# Board_V_1C.net
KiCad netlist of a schematic drawn in EAGLE
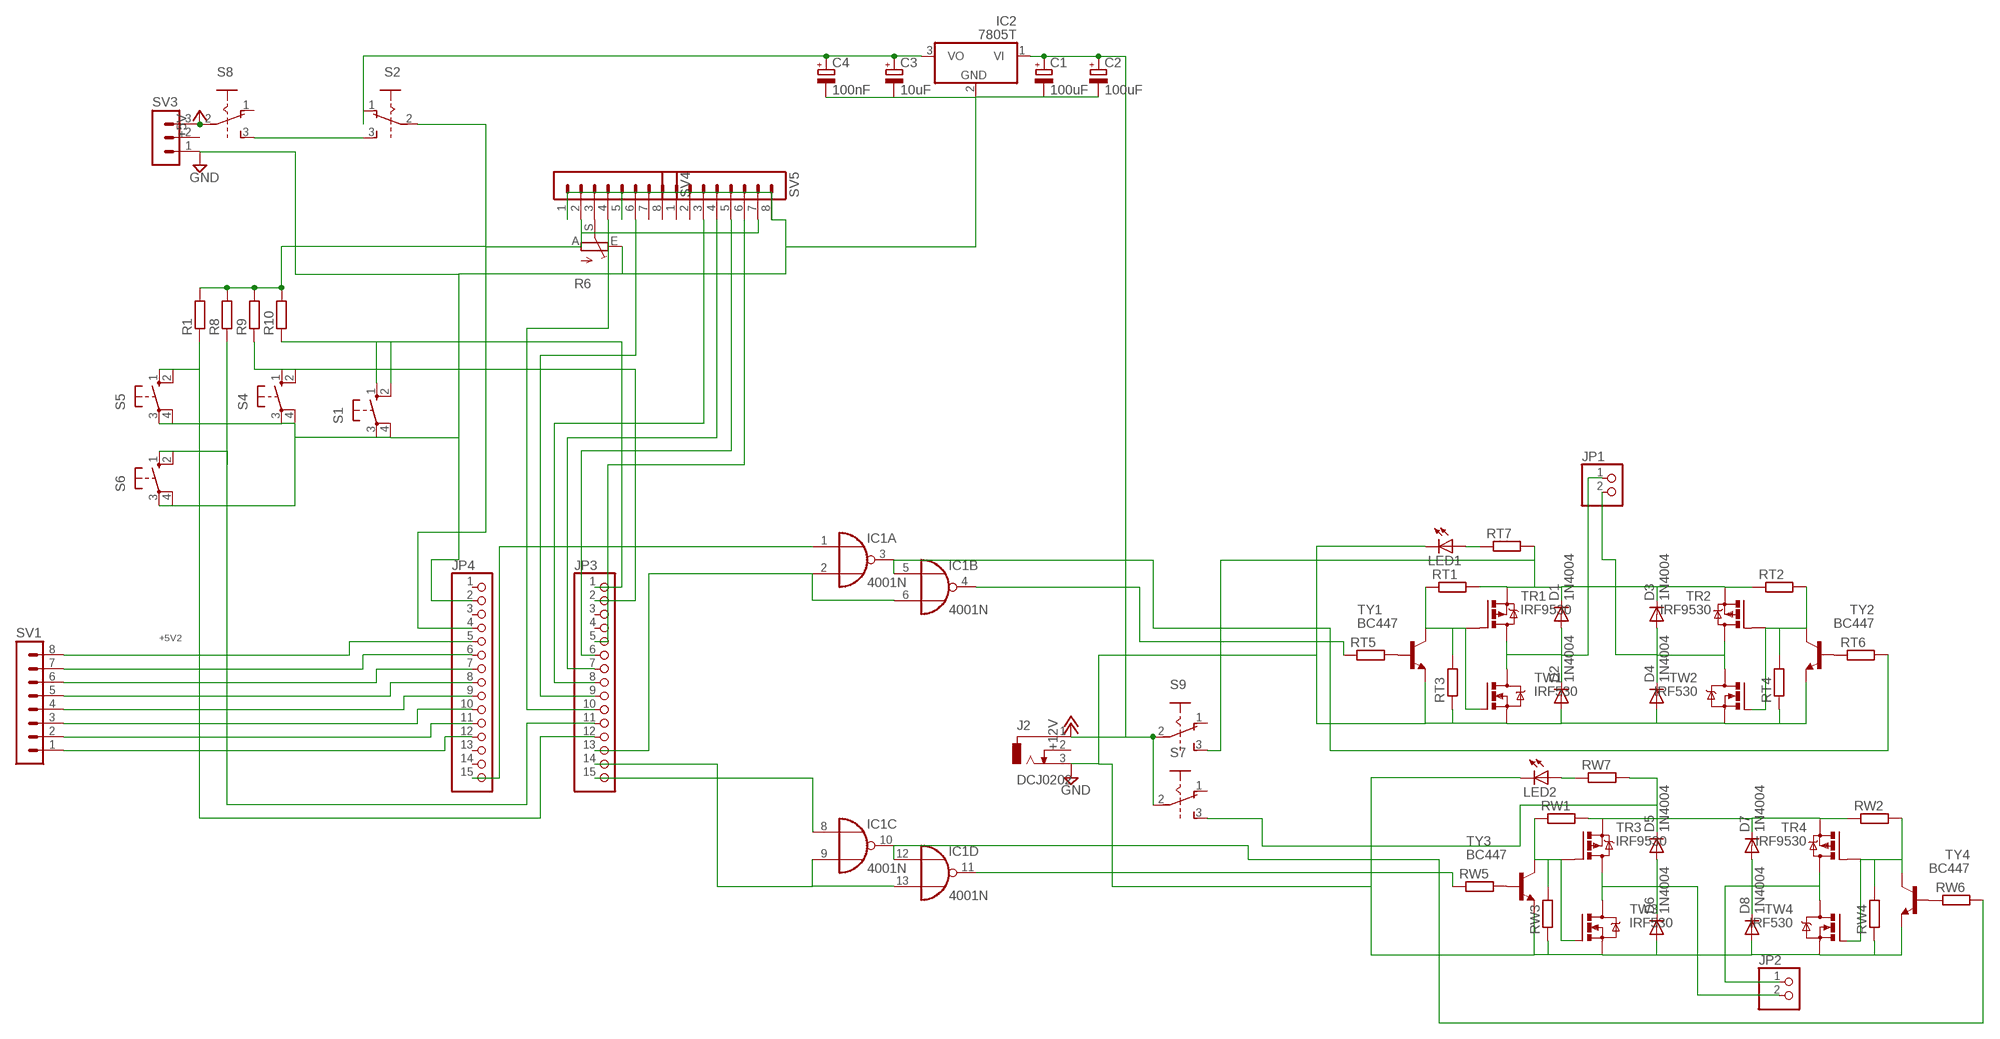
[diagram p0: schematic, sheet 1]

(export (version "E")
  (design (tool "Eeschema 10.0.6"))
  (components
    (comp (ref "C1")
      (value "100uF")
      (footprint "eagle-import:E2,5-6")
      (libsource (lib "eagle-import") (part "CPOL-EUE2.5-6"))
    )
    (comp (ref "C2")
      (value "100uF")
      (footprint "eagle-import:E2,5-6")
      (libsource (lib "eagle-import") (part "CPOL-EUE2.5-6"))
    )
    (comp (ref "C3")
      (value "10uF")
      (footprint "eagle-import:E2,5-6")
      (libsource (lib "eagle-import") (part "CPOL-EUE2.5-6"))
    )
    (comp (ref "C4")
      (value "100nF")
      (footprint "eagle-import:E2,5-6")
      (libsource (lib "eagle-import") (part "CPOL-EUE2.5-6"))
    )
    (comp (ref "D1")
      (value "1N4004")
      (footprint "eagle-import:DO41-10")
      (libsource (lib "eagle-import") (part "1N4004"))
    )
    (comp (ref "D2")
      (value "1N4004")
      (footprint "eagle-import:DO41-10")
      (libsource (lib "eagle-import") (part "1N4004"))
    )
    (comp (ref "D3")
      (value "1N4004")
      (footprint "eagle-import:DO41-10")
      (libsource (lib "eagle-import") (part "1N4004"))
    )
    (comp (ref "D4")
      (value "1N4004")
      (footprint "eagle-import:DO41-10")
      (libsource (lib "eagle-import") (part "1N4004"))
    )
    (comp (ref "D5")
      (value "1N4004")
      (footprint "eagle-import:DO41-10")
      (libsource (lib "eagle-import") (part "1N4004"))
    )
    (comp (ref "D6")
      (value "1N4004")
      (footprint "eagle-import:DO41-10")
      (libsource (lib "eagle-import") (part "1N4004"))
    )
    (comp (ref "D7")
      (value "1N4004")
      (footprint "eagle-import:DO41-10")
      (libsource (lib "eagle-import") (part "1N4004"))
    )
    (comp (ref "D8")
      (value "1N4004")
      (footprint "eagle-import:DO41-10")
      (libsource (lib "eagle-import") (part "1N4004"))
    )
    (comp (ref "IC1")
      (value "4001N")
      (footprint "eagle-import:DIL14")
      (libsource (lib "eagle-import") (part "4001N"))
    )
    (comp (ref "IC2")
      (value "7805T")
      (footprint "eagle-import:TO220H")
      (libsource (lib "eagle-import") (part "78T05"))
    )
    (comp (ref "J2")
      (value "DCJ0202")
      (footprint "eagle-import:DCJ0202")
      (libsource (lib "eagle-import") (part "DCJ0202"))
    )
    (comp (ref "JP1")
      (value "PINHD-1X2")
      (footprint "eagle-import:1X02")
      (libsource (lib "eagle-import") (part "PINHD-1X2"))
    )
    (comp (ref "JP2")
      (value "PINHD-1X2")
      (footprint "eagle-import:1X02")
      (libsource (lib "eagle-import") (part "PINHD-1X2"))
    )
    (comp (ref "JP3")
      (value "PINHD-1X15")
      (footprint "eagle-import:1X15")
      (libsource (lib "eagle-import") (part "PINHD-1X15"))
    )
    (comp (ref "JP4")
      (value "PINHD-1X15")
      (footprint "eagle-import:1X15")
      (libsource (lib "eagle-import") (part "PINHD-1X15"))
    )
    (comp (ref "LED1")
      (value "LED5MM")
      (footprint "eagle-import:LED5MM")
      (libsource (lib "eagle-import") (part "LED5MM"))
    )
    (comp (ref "LED2")
      (value "LED5MM")
      (footprint "eagle-import:LED5MM")
      (libsource (lib "eagle-import") (part "LED5MM"))
    )
    (comp (ref "R1")
      (value "R-EU_0204/7")
      (footprint "eagle-import:0204_7")
      (libsource (lib "eagle-import") (part "R-EU_0204/7"))
    )
    (comp (ref "R6")
      (value "TRIM_EU-B25P")
      (footprint "eagle-import:B25P")
      (libsource (lib "eagle-import") (part "TRIM_EU-B25P"))
    )
    (comp (ref "R8")
      (value "R-EU_0204/7")
      (footprint "eagle-import:0204_7")
      (libsource (lib "eagle-import") (part "R-EU_0204/7"))
    )
    (comp (ref "R9")
      (value "R-EU_0204/7")
      (footprint "eagle-import:0204_7")
      (libsource (lib "eagle-import") (part "R-EU_0204/7"))
    )
    (comp (ref "R10")
      (value "R-EU_0204/7")
      (footprint "eagle-import:0204_7")
      (libsource (lib "eagle-import") (part "R-EU_0204/7"))
    )
    (comp (ref "RT1")
      (value "R-EU_0207/7")
      (footprint "eagle-import:0207_7")
      (libsource (lib "eagle-import") (part "R-EU_0207/7"))
    )
    (comp (ref "RT2")
      (value "R-EU_0207/7")
      (footprint "eagle-import:0207_7")
      (libsource (lib "eagle-import") (part "R-EU_0207/7"))
    )
    (comp (ref "RT3")
      (value "R-EU_0207/7")
      (footprint "eagle-import:0207_7")
      (libsource (lib "eagle-import") (part "R-EU_0207/7"))
    )
    (comp (ref "RT4")
      (value "R-EU_0207/7")
      (footprint "eagle-import:0207_7")
      (libsource (lib "eagle-import") (part "R-EU_0207/7"))
    )
    (comp (ref "RT5")
      (value "R-EU_0207/7")
      (footprint "eagle-import:0207_7")
      (libsource (lib "eagle-import") (part "R-EU_0207/7"))
    )
    (comp (ref "RT6")
      (value "R-EU_0207/7")
      (footprint "eagle-import:0207_7")
      (libsource (lib "eagle-import") (part "R-EU_0207/7"))
    )
    (comp (ref "RT7")
      (value "R-EU_0207/7")
      (footprint "eagle-import:0207_7")
      (libsource (lib "eagle-import") (part "R-EU_0207/7"))
    )
    (comp (ref "RW1")
      (value "R-EU_0207/7")
      (footprint "eagle-import:0207_7")
      (libsource (lib "eagle-import") (part "R-EU_0207/7"))
    )
    (comp (ref "RW2")
      (value "R-EU_0207/7")
      (footprint "eagle-import:0207_7")
      (libsource (lib "eagle-import") (part "R-EU_0207/7"))
    )
    (comp (ref "RW3")
      (value "R-EU_0207/7")
      (footprint "eagle-import:0207_7")
      (libsource (lib "eagle-import") (part "R-EU_0207/7"))
    )
    (comp (ref "RW4")
      (value "R-EU_0207/7")
      (footprint "eagle-import:0207_7")
      (libsource (lib "eagle-import") (part "R-EU_0207/7"))
    )
    (comp (ref "RW5")
      (value "R-EU_0207/7")
      (footprint "eagle-import:0207_7")
      (libsource (lib "eagle-import") (part "R-EU_0207/7"))
    )
    (comp (ref "RW6")
      (value "R-EU_0207/7")
      (footprint "eagle-import:0207_7")
      (libsource (lib "eagle-import") (part "R-EU_0207/7"))
    )
    (comp (ref "RW7")
      (value "R-EU_0207/7")
      (footprint "eagle-import:0207_7")
      (libsource (lib "eagle-import") (part "R-EU_0207/7"))
    )
    (comp (ref "S1")
      (value "10-XX")
      (footprint "eagle-import:B3F-10XX")
      (libsource (lib "eagle-import") (part "10-XX"))
    )
    (comp (ref "S2")
      (value "A68-A31")
      (footprint "eagle-import:A68-A31")
      (libsource (lib "eagle-import") (part "A68-A31"))
    )
    (comp (ref "S4")
      (value "10-XX")
      (footprint "eagle-import:B3F-10XX")
      (libsource (lib "eagle-import") (part "10-XX"))
    )
    (comp (ref "S5")
      (value "10-XX")
      (footprint "eagle-import:B3F-10XX")
      (libsource (lib "eagle-import") (part "10-XX"))
    )
    (comp (ref "S6")
      (value "10-XX")
      (footprint "eagle-import:B3F-10XX")
      (libsource (lib "eagle-import") (part "10-XX"))
    )
    (comp (ref "S7")
      (value "A68-A31")
      (footprint "eagle-import:A68-A31")
      (libsource (lib "eagle-import") (part "A68-A31"))
    )
    (comp (ref "S8")
      (value "A68-A31")
      (footprint "eagle-import:A68-A31")
      (libsource (lib "eagle-import") (part "A68-A31"))
    )
    (comp (ref "S9")
      (value "A68-A31")
      (footprint "eagle-import:A68-A31")
      (libsource (lib "eagle-import") (part "A68-A31"))
    )
    (comp (ref "SV1")
      (value "MA08-1")
      (footprint "eagle-import:MA08-1")
      (libsource (lib "eagle-import") (part "MA08-1"))
    )
    (comp (ref "SV3")
      (value "MA03-1")
      (footprint "eagle-import:MA03-1")
      (libsource (lib "eagle-import") (part "MA03-1"))
    )
    (comp (ref "SV4")
      (value "MA08-1")
      (footprint "eagle-import:MA08-1")
      (libsource (lib "eagle-import") (part "MA08-1"))
    )
    (comp (ref "SV5")
      (value "MA08-1")
      (footprint "eagle-import:MA08-1")
      (libsource (lib "eagle-import") (part "MA08-1"))
    )
    (comp (ref "TR1")
      (value "IRF9530")
      (footprint "eagle-import:TO220BV")
      (libsource (lib "eagle-import") (part "IRF9530"))
    )
    (comp (ref "TR2")
      (value "IRF9530")
      (footprint "eagle-import:TO220BV")
      (libsource (lib "eagle-import") (part "IRF9530"))
    )
    (comp (ref "TR3")
      (value "IRF9530")
      (footprint "eagle-import:TO220BV")
      (libsource (lib "eagle-import") (part "IRF9530"))
    )
    (comp (ref "TR4")
      (value "IRF9530")
      (footprint "eagle-import:TO220BV")
      (libsource (lib "eagle-import") (part "IRF9530"))
    )
    (comp (ref "TW1")
      (value "IRF530")
      (footprint "eagle-import:TO220BV")
      (libsource (lib "eagle-import") (part "IRF530"))
    )
    (comp (ref "TW2")
      (value "IRF530")
      (footprint "eagle-import:TO220BV")
      (libsource (lib "eagle-import") (part "IRF530"))
    )
    (comp (ref "TW3")
      (value "IRF530")
      (footprint "eagle-import:TO220BV")
      (libsource (lib "eagle-import") (part "IRF530"))
    )
    (comp (ref "TW4")
      (value "IRF530")
      (footprint "eagle-import:TO220BV")
      (libsource (lib "eagle-import") (part "IRF530"))
    )
    (comp (ref "TY1")
      (value "BC447")
      (footprint "eagle-import:TO92-EBC")
      (libsource (lib "eagle-import") (part "BC447"))
    )
    (comp (ref "TY2")
      (value "BC447")
      (footprint "eagle-import:TO92-EBC")
      (libsource (lib "eagle-import") (part "BC447"))
    )
    (comp (ref "TY3")
      (value "BC447")
      (footprint "eagle-import:TO92-EBC")
      (libsource (lib "eagle-import") (part "BC447"))
    )
    (comp (ref "TY4")
      (value "BC447")
      (footprint "eagle-import:TO92-EBC")
      (libsource (lib "eagle-import") (part "BC447"))
    )
  )
  (nets
    (net (code "1") (name "+5V") (class "Default")
      (node (ref "S8") (pin "2") (pinfunction "P_2") (pintype "passive"))
      (node (ref "SV3") (pin "3") (pinfunction "3_3") (pintype "passive"))
    )
    (net (code "2") (name "+12V") (class "Default")
      (node (ref "C1") (pin "+") (pinfunction "+_+") (pintype "passive"))
      (node (ref "C2") (pin "+") (pinfunction "+_+") (pintype "passive"))
      (node (ref "IC2") (pin "1") (pinfunction "VI_1") (pintype "input"))
      (node (ref "J2") (pin "1") (pinfunction "1_1") (pintype "passive"))
      (node (ref "S7") (pin "2") (pinfunction "P_2") (pintype "passive"))
      (node (ref "S9") (pin "2") (pinfunction "P_2") (pintype "passive"))
    )
    (net (code "3") (name "/+5V2") (class "Default")
      (node (ref "JP4") (pin "4") (pinfunction "4_4") (pintype "passive"))
      (node (ref "R1") (pin "2") (pinfunction "2_2") (pintype "passive"))
      (node (ref "R10") (pin "2") (pinfunction "2_2") (pintype "passive"))
      (node (ref "R6") (pin "A") (pinfunction "A_A") (pintype "passive"))
      (node (ref "R8") (pin "2") (pinfunction "2_2") (pintype "passive"))
      (node (ref "R9") (pin "2") (pinfunction "2_2") (pintype "passive"))
      (node (ref "S2") (pin "2") (pinfunction "P_2") (pintype "passive"))
      (node (ref "SV4") (pin "2") (pinfunction "2_2") (pintype "passive"))
      (node (ref "SV5") (pin "7") (pinfunction "7_7") (pintype "passive"))
    )
    (net (code "4") (name "GND") (class "Default")
      (node (ref "C1") (pin "-") (pinfunction "-_-") (pintype "passive"))
      (node (ref "C2") (pin "-") (pinfunction "-_-") (pintype "passive"))
      (node (ref "C3") (pin "-") (pinfunction "-_-") (pintype "passive"))
      (node (ref "C4") (pin "-") (pinfunction "-_-") (pintype "passive"))
      (node (ref "D2") (pin "A") (pinfunction "A_A") (pintype "passive"))
      (node (ref "D4") (pin "A") (pinfunction "A_A") (pintype "passive"))
      (node (ref "D6") (pin "A") (pinfunction "A_A") (pintype "passive"))
      (node (ref "D8") (pin "A") (pinfunction "A_A") (pintype "passive"))
      (node (ref "IC2") (pin "2") (pinfunction "GND_2") (pintype "passive"))
      (node (ref "J2") (pin "3") (pinfunction "3_3") (pintype "passive"))
      (node (ref "JP4") (pin "2") (pinfunction "2_2") (pintype "passive"))
      (node (ref "LED1") (pin "K") (pinfunction "C_K") (pintype "passive"))
      (node (ref "LED2") (pin "K") (pinfunction "C_K") (pintype "passive"))
      (node (ref "R6") (pin "E") (pinfunction "E_E") (pintype "passive"))
      (node (ref "RT3") (pin "1") (pinfunction "1_1") (pintype "passive"))
      (node (ref "RT4") (pin "1") (pinfunction "1_1") (pintype "passive"))
      (node (ref "RW3") (pin "1") (pinfunction "1_1") (pintype "passive"))
      (node (ref "RW4") (pin "1") (pinfunction "1_1") (pintype "passive"))
      (node (ref "S1") (pin "3") (pinfunction "P_3") (pintype "passive"))
      (node (ref "S1") (pin "4") (pinfunction "P1_4") (pintype "passive"))
      (node (ref "S4") (pin "3") (pinfunction "P_3") (pintype "passive"))
      (node (ref "S4") (pin "4") (pinfunction "P1_4") (pintype "passive"))
      (node (ref "S5") (pin "3") (pinfunction "P_3") (pintype "passive"))
      (node (ref "S5") (pin "4") (pinfunction "P1_4") (pintype "passive"))
      (node (ref "S6") (pin "3") (pinfunction "P_3") (pintype "passive"))
      (node (ref "S6") (pin "4") (pinfunction "P1_4") (pintype "passive"))
      (node (ref "SV3") (pin "1") (pinfunction "1_1") (pintype "passive"))
      (node (ref "SV4") (pin "1") (pinfunction "1_1") (pintype "passive"))
      (node (ref "SV4") (pin "5") (pinfunction "5_5") (pintype "passive"))
      (node (ref "SV5") (pin "8") (pinfunction "8_8") (pintype "passive"))
      (node (ref "TW1") (pin "S") (pinfunction "S_S") (pintype "passive"))
      (node (ref "TW2") (pin "S") (pinfunction "S_S") (pintype "passive"))
      (node (ref "TW3") (pin "S") (pinfunction "S_S") (pintype "passive"))
      (node (ref "TW4") (pin "S") (pinfunction "S_S") (pintype "passive"))
      (node (ref "TY1") (pin "E") (pinfunction "E_E") (pintype "passive"))
      (node (ref "TY2") (pin "E") (pinfunction "E_E") (pintype "passive"))
      (node (ref "TY3") (pin "E") (pinfunction "E_E") (pintype "passive"))
      (node (ref "TY4") (pin "E") (pinfunction "E_E") (pintype "passive"))
    )
    (net (code "5") (name "Net-(D1-PadA)") (class "Default")
      (node (ref "D1") (pin "A") (pinfunction "A_A") (pintype "passive"))
      (node (ref "D2") (pin "C") (pinfunction "C_C") (pintype "passive"))
      (node (ref "JP1") (pin "1") (pinfunction "1_1") (pintype "passive"))
      (node (ref "TR1") (pin "D") (pinfunction "D_D") (pintype "passive"))
      (node (ref "TW1") (pin "D") (pinfunction "D_D") (pintype "passive"))
    )
    (net (code "6") (name "Net-(D3-PadA)") (class "Default")
      (node (ref "D3") (pin "A") (pinfunction "A_A") (pintype "passive"))
      (node (ref "D4") (pin "C") (pinfunction "C_C") (pintype "passive"))
      (node (ref "JP1") (pin "2") (pinfunction "2_2") (pintype "passive"))
      (node (ref "TR2") (pin "D") (pinfunction "D_D") (pintype "passive"))
      (node (ref "TW2") (pin "D") (pinfunction "D_D") (pintype "passive"))
    )
    (net (code "7") (name "Net-(D5-PadA)") (class "Default")
      (node (ref "D5") (pin "A") (pinfunction "A_A") (pintype "passive"))
      (node (ref "D6") (pin "C") (pinfunction "C_C") (pintype "passive"))
      (node (ref "JP2") (pin "2") (pinfunction "2_2") (pintype "passive"))
      (node (ref "TR3") (pin "D") (pinfunction "D_D") (pintype "passive"))
      (node (ref "TW3") (pin "D") (pinfunction "D_D") (pintype "passive"))
    )
    (net (code "8") (name "Net-(D7-PadA)") (class "Default")
      (node (ref "D7") (pin "A") (pinfunction "A_A") (pintype "passive"))
      (node (ref "D8") (pin "C") (pinfunction "C_C") (pintype "passive"))
      (node (ref "JP2") (pin "1") (pinfunction "1_1") (pintype "passive"))
      (node (ref "TR4") (pin "D") (pinfunction "D_D") (pintype "passive"))
      (node (ref "TW4") (pin "D") (pinfunction "D_D") (pintype "passive"))
    )
    (net (code "9") (name "Net-(IC1A-I0)") (class "Default")
      (node (ref "IC1") (pin "1") (pinfunction "I0_1") (pintype "input"))
      (node (ref "JP4") (pin "15") (pinfunction "15_15") (pintype "passive"))
    )
    (net (code "10") (name "Net-(IC1A-I1)") (class "Default")
      (node (ref "IC1") (pin "2") (pinfunction "I1_2") (pintype "input"))
      (node (ref "IC1") (pin "6") (pinfunction "I1_6") (pintype "input"))
      (node (ref "JP3") (pin "13") (pinfunction "13_13") (pintype "passive"))
    )
    (net (code "11") (name "Net-(IC1A-O)") (class "Default")
      (node (ref "IC1") (pin "3") (pinfunction "O_3") (pintype "output"))
      (node (ref "IC1") (pin "5") (pinfunction "I0_5") (pintype "input"))
      (node (ref "RT6") (pin "2") (pinfunction "2_2") (pintype "passive"))
    )
    (net (code "12") (name "Net-(IC1B-O)") (class "Default")
      (node (ref "IC1") (pin "4") (pinfunction "O_4") (pintype "output"))
      (node (ref "RT5") (pin "1") (pinfunction "1_1") (pintype "passive"))
    )
    (net (code "13") (name "Net-(IC1C-I0)") (class "Default")
      (node (ref "IC1") (pin "8") (pinfunction "I0_8") (pintype "input"))
      (node (ref "JP3") (pin "15") (pinfunction "15_15") (pintype "passive"))
    )
    (net (code "14") (name "Net-(IC1C-I1)") (class "Default")
      (node (ref "IC1") (pin "13") (pinfunction "I1_13") (pintype "input"))
      (node (ref "IC1") (pin "9") (pinfunction "I1_9") (pintype "input"))
      (node (ref "JP3") (pin "14") (pinfunction "14_14") (pintype "passive"))
    )
    (net (code "15") (name "Net-(IC1C-O)") (class "Default")
      (node (ref "IC1") (pin "10") (pinfunction "O_10") (pintype "output"))
      (node (ref "IC1") (pin "12") (pinfunction "I0_12") (pintype "input"))
      (node (ref "RW6") (pin "2") (pinfunction "2_2") (pintype "passive"))
    )
    (net (code "16") (name "Net-(IC1D-O)") (class "Default")
      (node (ref "IC1") (pin "11") (pinfunction "O_11") (pintype "output"))
      (node (ref "RW5") (pin "1") (pinfunction "1_1") (pintype "passive"))
    )
    (net (code "17") (name "Net-(IC2-VO)") (class "Default")
      (node (ref "C3") (pin "+") (pinfunction "+_+") (pintype "passive"))
      (node (ref "C4") (pin "+") (pinfunction "+_+") (pintype "passive"))
      (node (ref "IC2") (pin "3") (pinfunction "VO_3") (pintype "passive"))
    )
    (net (code "18") (name "Net-(JP3-Pad5)") (class "Default")
      (node (ref "JP3") (pin "5") (pinfunction "5_5") (pintype "passive"))
      (node (ref "SV5") (pin "6") (pinfunction "6_6") (pintype "passive"))
    )
    (net (code "19") (name "Net-(JP3-Pad6)") (class "Default")
      (node (ref "JP3") (pin "6") (pinfunction "6_6") (pintype "passive"))
      (node (ref "SV5") (pin "5") (pinfunction "5_5") (pintype "passive"))
    )
    (net (code "20") (name "Net-(JP3-Pad7)") (class "Default")
      (node (ref "JP3") (pin "7") (pinfunction "7_7") (pintype "passive"))
      (node (ref "SV5") (pin "4") (pinfunction "4_4") (pintype "passive"))
    )
    (net (code "21") (name "Net-(JP3-Pad8)") (class "Default")
      (node (ref "JP3") (pin "8") (pinfunction "8_8") (pintype "passive"))
      (node (ref "SV5") (pin "3") (pinfunction "3_3") (pintype "passive"))
    )
    (net (code "22") (name "Net-(JP3-Pad9)") (class "Default")
      (node (ref "JP3") (pin "9") (pinfunction "9_9") (pintype "passive"))
      (node (ref "SV4") (pin "6") (pinfunction "6_6") (pintype "passive"))
    )
    (net (code "23") (name "Net-(JP3-Pad10)") (class "Default")
      (node (ref "JP3") (pin "10") (pinfunction "10_10") (pintype "passive"))
      (node (ref "SV4") (pin "4") (pinfunction "4_4") (pintype "passive"))
    )
    (net (code "24") (name "Net-(JP4-Pad5)") (class "Default")
      (node (ref "JP4") (pin "5") (pinfunction "5_5") (pintype "passive"))
      (node (ref "SV1") (pin "8") (pinfunction "8_8") (pintype "passive"))
    )
    (net (code "25") (name "Net-(JP4-Pad6)") (class "Default")
      (node (ref "JP4") (pin "6") (pinfunction "6_6") (pintype "passive"))
      (node (ref "SV1") (pin "7") (pinfunction "7_7") (pintype "passive"))
    )
    (net (code "26") (name "Net-(JP4-Pad7)") (class "Default")
      (node (ref "JP4") (pin "7") (pinfunction "7_7") (pintype "passive"))
      (node (ref "SV1") (pin "6") (pinfunction "6_6") (pintype "passive"))
    )
    (net (code "27") (name "Net-(JP4-Pad8)") (class "Default")
      (node (ref "JP4") (pin "8") (pinfunction "8_8") (pintype "passive"))
      (node (ref "SV1") (pin "5") (pinfunction "5_5") (pintype "passive"))
    )
    (net (code "28") (name "Net-(JP4-Pad9)") (class "Default")
      (node (ref "JP4") (pin "9") (pinfunction "9_9") (pintype "passive"))
      (node (ref "SV1") (pin "4") (pinfunction "4_4") (pintype "passive"))
    )
    (net (code "29") (name "Net-(JP4-Pad10)") (class "Default")
      (node (ref "JP4") (pin "10") (pinfunction "10_10") (pintype "passive"))
      (node (ref "SV1") (pin "3") (pinfunction "3_3") (pintype "passive"))
    )
    (net (code "30") (name "Net-(JP4-Pad11)") (class "Default")
      (node (ref "JP4") (pin "11") (pinfunction "11_11") (pintype "passive"))
      (node (ref "SV1") (pin "2") (pinfunction "2_2") (pintype "passive"))
    )
    (net (code "31") (name "Net-(JP4-Pad12)") (class "Default")
      (node (ref "JP4") (pin "12") (pinfunction "12_12") (pintype "passive"))
      (node (ref "SV1") (pin "1") (pinfunction "1_1") (pintype "passive"))
    )
    (net (code "32") (name "Net-(LED1-PadA)") (class "Default")
      (node (ref "LED1") (pin "A") (pinfunction "A_A") (pintype "passive"))
      (node (ref "RT7") (pin "1") (pinfunction "1_1") (pintype "passive"))
    )
    (net (code "33") (name "Net-(LED2-PadA)") (class "Default")
      (node (ref "LED2") (pin "A") (pinfunction "A_A") (pintype "passive"))
      (node (ref "RW7") (pin "1") (pinfunction "1_1") (pintype "passive"))
    )
    (net (code "34") (name "Net-(R6-PadS)") (class "Default")
      (node (ref "R6") (pin "S") (pinfunction "S_S") (pintype "passive"))
      (node (ref "SV4") (pin "3") (pinfunction "3_3") (pintype "passive"))
    )
    (net (code "35") (name "Net-(RT1-Pad1)") (class "Default")
      (node (ref "RT1") (pin "1") (pinfunction "1_1") (pintype "passive"))
      (node (ref "RT3") (pin "2") (pinfunction "2_2") (pintype "passive"))
      (node (ref "TR1") (pin "G") (pinfunction "G_G") (pintype "passive"))
      (node (ref "TW1") (pin "G") (pinfunction "G_G") (pintype "passive"))
      (node (ref "TY1") (pin "C") (pinfunction "C_C") (pintype "passive"))
    )
    (net (code "36") (name "Net-(RT2-Pad2)") (class "Default")
      (node (ref "RT2") (pin "2") (pinfunction "2_2") (pintype "passive"))
      (node (ref "RT4") (pin "2") (pinfunction "2_2") (pintype "passive"))
      (node (ref "TR2") (pin "G") (pinfunction "G_G") (pintype "passive"))
      (node (ref "TW2") (pin "G") (pinfunction "G_G") (pintype "passive"))
      (node (ref "TY2") (pin "C") (pinfunction "C_C") (pintype "passive"))
    )
    (net (code "37") (name "Net-(RT5-Pad2)") (class "Default")
      (node (ref "RT5") (pin "2") (pinfunction "2_2") (pintype "passive"))
      (node (ref "TY1") (pin "B") (pinfunction "B_B") (pintype "passive"))
    )
    (net (code "38") (name "Net-(RT6-Pad1)") (class "Default")
      (node (ref "RT6") (pin "1") (pinfunction "1_1") (pintype "passive"))
      (node (ref "TY2") (pin "B") (pinfunction "B_B") (pintype "passive"))
    )
    (net (code "39") (name "Net-(RW1-Pad1)") (class "Default")
      (node (ref "RW1") (pin "1") (pinfunction "1_1") (pintype "passive"))
      (node (ref "RW3") (pin "2") (pinfunction "2_2") (pintype "passive"))
      (node (ref "TR3") (pin "G") (pinfunction "G_G") (pintype "passive"))
      (node (ref "TW3") (pin "G") (pinfunction "G_G") (pintype "passive"))
      (node (ref "TY3") (pin "C") (pinfunction "C_C") (pintype "passive"))
    )
    (net (code "40") (name "Net-(RW2-Pad2)") (class "Default")
      (node (ref "RW2") (pin "2") (pinfunction "2_2") (pintype "passive"))
      (node (ref "RW4") (pin "2") (pinfunction "2_2") (pintype "passive"))
      (node (ref "TR4") (pin "G") (pinfunction "G_G") (pintype "passive"))
      (node (ref "TW4") (pin "G") (pinfunction "G_G") (pintype "passive"))
      (node (ref "TY4") (pin "C") (pinfunction "C_C") (pintype "passive"))
    )
    (net (code "41") (name "Net-(RW5-Pad2)") (class "Default")
      (node (ref "RW5") (pin "2") (pinfunction "2_2") (pintype "passive"))
      (node (ref "TY3") (pin "B") (pinfunction "B_B") (pintype "passive"))
    )
    (net (code "42") (name "Net-(RW6-Pad1)") (class "Default")
      (node (ref "RW6") (pin "1") (pinfunction "1_1") (pintype "passive"))
      (node (ref "TY4") (pin "B") (pinfunction "B_B") (pintype "passive"))
    )
    (net (code "43") (name "Net-(S1-S)") (class "Default")
      (node (ref "JP3") (pin "1") (pinfunction "1_1") (pintype "passive"))
      (node (ref "R10") (pin "1") (pinfunction "1_1") (pintype "passive"))
      (node (ref "S1") (pin "1") (pinfunction "S_1") (pintype "passive"))
      (node (ref "S1") (pin "2") (pinfunction "S1_2") (pintype "passive"))
    )
    (net (code "44") (name "Net-(S2A-S)") (class "Default")
      (node (ref "S2") (pin "3") (pinfunction "S_3") (pintype "passive"))
      (node (ref "S8") (pin "3") (pinfunction "S_3") (pintype "passive"))
    )
    (net (code "45") (name "Net-(S4-S)") (class "Default")
      (node (ref "JP3") (pin "2") (pinfunction "2_2") (pintype "passive"))
      (node (ref "R9") (pin "1") (pinfunction "1_1") (pintype "passive"))
      (node (ref "S4") (pin "1") (pinfunction "S_1") (pintype "passive"))
      (node (ref "S4") (pin "2") (pinfunction "S1_2") (pintype "passive"))
    )
    (net (code "46") (name "Net-(S5-S)") (class "Default")
      (node (ref "JP3") (pin "12") (pinfunction "12_12") (pintype "passive"))
      (node (ref "R1") (pin "1") (pinfunction "1_1") (pintype "passive"))
      (node (ref "S5") (pin "1") (pinfunction "S_1") (pintype "passive"))
      (node (ref "S5") (pin "2") (pinfunction "S1_2") (pintype "passive"))
    )
    (net (code "47") (name "Net-(S6-S)") (class "Default")
      (node (ref "JP3") (pin "11") (pinfunction "11_11") (pintype "passive"))
      (node (ref "R8") (pin "1") (pinfunction "1_1") (pintype "passive"))
      (node (ref "S6") (pin "1") (pinfunction "S_1") (pintype "passive"))
      (node (ref "S6") (pin "2") (pinfunction "S1_2") (pintype "passive"))
    )
    (net (code "48") (name "Net-(S7A-S)") (class "Default")
      (node (ref "D5") (pin "C") (pinfunction "C_C") (pintype "passive"))
      (node (ref "D7") (pin "C") (pinfunction "C_C") (pintype "passive"))
      (node (ref "RW1") (pin "2") (pinfunction "2_2") (pintype "passive"))
      (node (ref "RW2") (pin "1") (pinfunction "1_1") (pintype "passive"))
      (node (ref "RW7") (pin "2") (pinfunction "2_2") (pintype "passive"))
      (node (ref "S7") (pin "3") (pinfunction "S_3") (pintype "passive"))
      (node (ref "TR3") (pin "S") (pinfunction "S_S") (pintype "passive"))
      (node (ref "TR4") (pin "S") (pinfunction "S_S") (pintype "passive"))
    )
    (net (code "49") (name "Net-(S9A-S)") (class "Default")
      (node (ref "D1") (pin "C") (pinfunction "C_C") (pintype "passive"))
      (node (ref "D3") (pin "C") (pinfunction "C_C") (pintype "passive"))
      (node (ref "RT1") (pin "2") (pinfunction "2_2") (pintype "passive"))
      (node (ref "RT2") (pin "1") (pinfunction "1_1") (pintype "passive"))
      (node (ref "RT7") (pin "2") (pinfunction "2_2") (pintype "passive"))
      (node (ref "S9") (pin "3") (pinfunction "S_3") (pintype "passive"))
      (node (ref "TR1") (pin "S") (pinfunction "S_S") (pintype "passive"))
      (node (ref "TR2") (pin "S") (pinfunction "S_S") (pintype "passive"))
    )
    (net (code "50") (name "unconnected-(J2-Pad2)") (class "Default")
      (node (ref "J2") (pin "2") (pinfunction "2_2") (pintype "passive"))
    )
    (net (code "51") (name "unconnected-(JP3-Pad3)") (class "Default")
      (node (ref "JP3") (pin "3") (pinfunction "3_3") (pintype "passive"))
    )
    (net (code "52") (name "unconnected-(JP3-Pad4)") (class "Default")
      (node (ref "JP3") (pin "4") (pinfunction "4_4") (pintype "passive"))
    )
    (net (code "53") (name "unconnected-(JP4-Pad1)") (class "Default")
      (node (ref "JP4") (pin "1") (pinfunction "1_1") (pintype "passive"))
    )
    (net (code "54") (name "unconnected-(JP4-Pad3)") (class "Default")
      (node (ref "JP4") (pin "3") (pinfunction "3_3") (pintype "passive"))
    )
    (net (code "55") (name "unconnected-(JP4-Pad13)") (class "Default")
      (node (ref "JP4") (pin "13") (pinfunction "13_13") (pintype "passive"))
    )
    (net (code "56") (name "unconnected-(JP4-Pad14)") (class "Default")
      (node (ref "JP4") (pin "14") (pinfunction "14_14") (pintype "passive"))
    )
    (net (code "57") (name "unconnected-(S2A-O-Pad1)") (class "Default")
      (node (ref "S2") (pin "1") (pinfunction "O_1") (pintype "passive"))
    )
    (net (code "58") (name "unconnected-(S7A-O-Pad1)") (class "Default")
      (node (ref "S7") (pin "1") (pinfunction "O_1") (pintype "passive"))
    )
    (net (code "59") (name "unconnected-(S8A-O-Pad1)") (class "Default")
      (node (ref "S8") (pin "1") (pinfunction "O_1") (pintype "passive"))
    )
    (net (code "60") (name "unconnected-(S9A-O-Pad1)") (class "Default")
      (node (ref "S9") (pin "1") (pinfunction "O_1") (pintype "passive"))
    )
    (net (code "61") (name "unconnected-(SV3-Pad2)") (class "Default")
      (node (ref "SV3") (pin "2") (pinfunction "2_2") (pintype "passive"))
    )
    (net (code "62") (name "unconnected-(SV4-Pad7)") (class "Default")
      (node (ref "SV4") (pin "7") (pinfunction "7_7") (pintype "passive"))
    )
    (net (code "63") (name "unconnected-(SV4-Pad8)") (class "Default")
      (node (ref "SV4") (pin "8") (pinfunction "8_8") (pintype "passive"))
    )
    (net (code "64") (name "unconnected-(SV5-Pad1)") (class "Default")
      (node (ref "SV5") (pin "1") (pinfunction "1_1") (pintype "passive"))
    )
    (net (code "65") (name "unconnected-(SV5-Pad2)") (class "Default")
      (node (ref "SV5") (pin "2") (pinfunction "2_2") (pintype "passive"))
    )
  )
)
